# ABS_converter.net
KiCad netlist of a schematic drawn in EAGLE
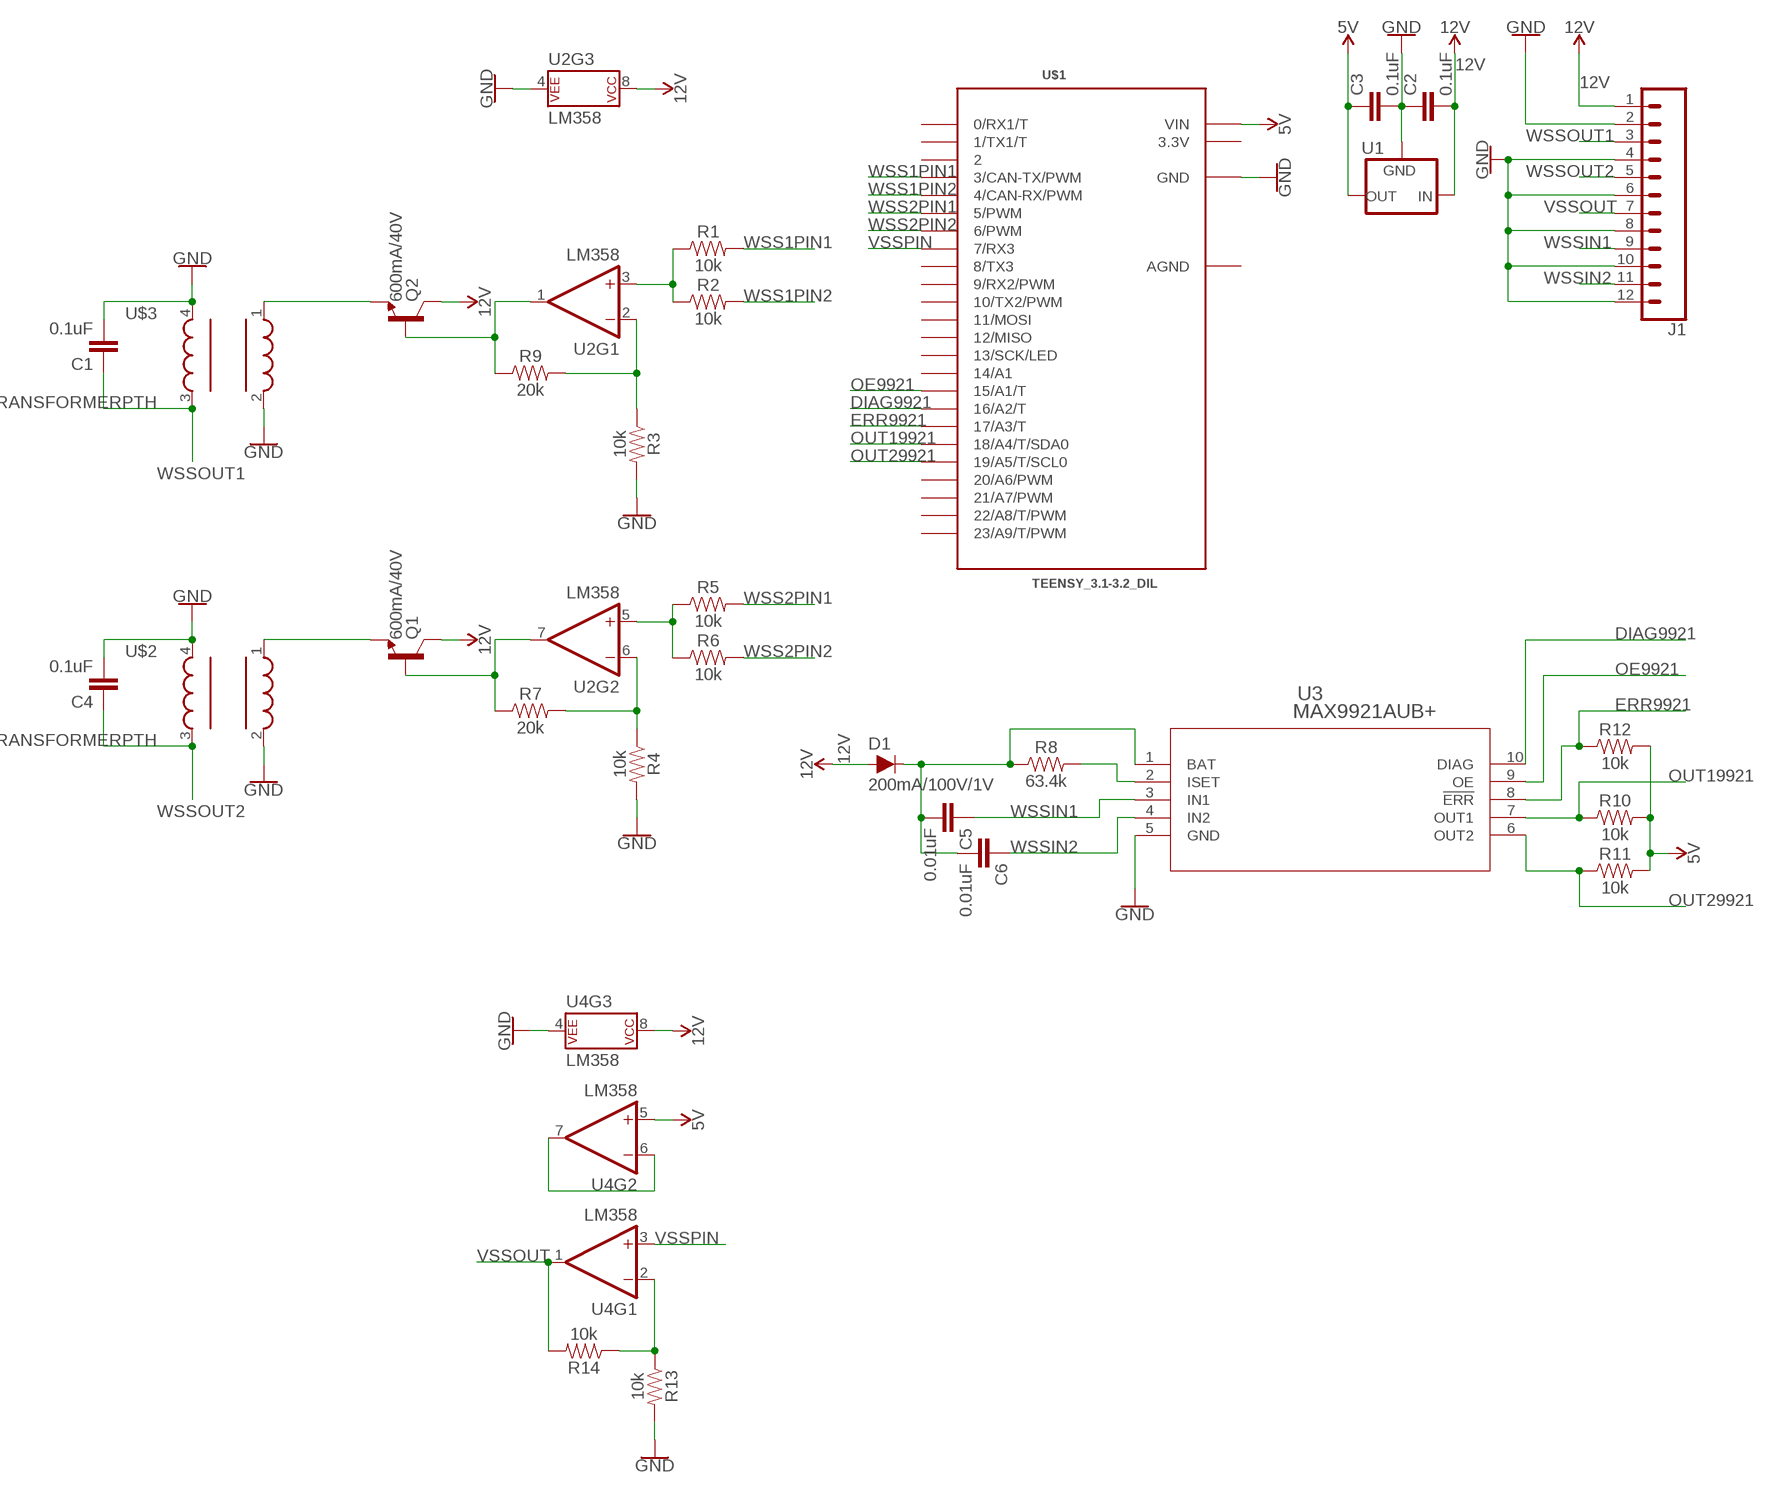
[diagram p0: schematic, sheet 1]

(export (version "E")
  (design (tool "Eeschema 10.0.6"))
  (components
    (comp (ref "C1")
      (value "0.1uF")
      (footprint "eagle-import:CAP-PTH-SMALL-KIT")
      (libsource (lib "eagle-import") (part "0.1UF-KIT-EZ-50V-20%"))
    )
    (comp (ref "C2")
      (value "0.1uF")
      (footprint "eagle-import:CAP-PTH-SMALL-KIT")
      (libsource (lib "eagle-import") (part "0.1UF-KIT-EZ-50V-20%"))
    )
    (comp (ref "C3")
      (value "0.1uF")
      (footprint "eagle-import:CAP-PTH-SMALL-KIT")
      (libsource (lib "eagle-import") (part "0.1UF-KIT-EZ-50V-20%"))
    )
    (comp (ref "C4")
      (value "0.1uF")
      (footprint "eagle-import:CAP-PTH-SMALL-KIT")
      (libsource (lib "eagle-import") (part "0.1UF-KIT-EZ-50V-20%"))
    )
    (comp (ref "C5")
      (value "0.01uF")
      (footprint "eagle-import:CAP-PTH-SMALL-KIT")
      (libsource (lib "eagle-import") (part "0.1UF-KIT-EZ-50V-20%"))
    )
    (comp (ref "C6")
      (value "0.01uF")
      (footprint "eagle-import:CAP-PTH-SMALL-KIT")
      (libsource (lib "eagle-import") (part "0.1UF-KIT-EZ-50V-20%"))
    )
    (comp (ref "D1")
      (value "200mA/100V/1V")
      (footprint "eagle-import:DIODE-1N4148")
      (libsource (lib "eagle-import") (part "DIODE-1N4148"))
    )
    (comp (ref "J1")
      (value "CONN_12")
      (footprint "eagle-import:1X12")
      (libsource (lib "eagle-import") (part "CONN_12"))
    )
    (comp (ref "Q1")
      (value "600mA/40V")
      (footprint "eagle-import:TO-92")
      (libsource (lib "eagle-import") (part "TRANS_NPN-P2N2222A"))
    )
    (comp (ref "Q2")
      (value "600mA/40V")
      (footprint "eagle-import:TO-92")
      (libsource (lib "eagle-import") (part "TRANS_NPN-P2N2222A"))
    )
    (comp (ref "R1")
      (value "10k")
      (footprint "eagle-import:AXIAL-0.3")
      (libsource (lib "eagle-import") (part "10KOHM-HORIZ-1/4W-1%"))
    )
    (comp (ref "R2")
      (value "10k")
      (footprint "eagle-import:AXIAL-0.3")
      (libsource (lib "eagle-import") (part "10KOHM-HORIZ-1/4W-1%"))
    )
    (comp (ref "R3")
      (value "10k")
      (footprint "eagle-import:AXIAL-0.3")
      (libsource (lib "eagle-import") (part "10KOHM-HORIZ-1/4W-1%"))
    )
    (comp (ref "R4")
      (value "10k")
      (footprint "eagle-import:AXIAL-0.3")
      (libsource (lib "eagle-import") (part "10KOHM-HORIZ-1/4W-1%"))
    )
    (comp (ref "R5")
      (value "10k")
      (footprint "eagle-import:AXIAL-0.3")
      (libsource (lib "eagle-import") (part "10KOHM-HORIZ-1/4W-1%"))
    )
    (comp (ref "R6")
      (value "10k")
      (footprint "eagle-import:AXIAL-0.3")
      (libsource (lib "eagle-import") (part "10KOHM-HORIZ-1/4W-1%"))
    )
    (comp (ref "R7")
      (value "20k")
      (footprint "eagle-import:AXIAL-0.3")
      (libsource (lib "eagle-import") (part "RESISTORAXIAL-0.3"))
    )
    (comp (ref "R8")
      (value "63.4k")
      (footprint "eagle-import:AXIAL-0.3")
      (libsource (lib "eagle-import") (part "RESISTORAXIAL-0.3"))
    )
    (comp (ref "R9")
      (value "20k")
      (footprint "eagle-import:AXIAL-0.3")
      (libsource (lib "eagle-import") (part "RESISTORAXIAL-0.3"))
    )
    (comp (ref "R10")
      (value "10k")
      (footprint "eagle-import:AXIAL-0.3")
      (libsource (lib "eagle-import") (part "10KOHM-HORIZ-1/4W-1%"))
    )
    (comp (ref "R11")
      (value "10k")
      (footprint "eagle-import:AXIAL-0.3")
      (libsource (lib "eagle-import") (part "10KOHM-HORIZ-1/4W-1%"))
    )
    (comp (ref "R12")
      (value "10k")
      (footprint "eagle-import:AXIAL-0.3")
      (libsource (lib "eagle-import") (part "10KOHM-HORIZ-1/4W-1%"))
    )
    (comp (ref "R13")
      (value "10k")
      (footprint "eagle-import:AXIAL-0.3")
      (libsource (lib "eagle-import") (part "10KOHM-HORIZ-1/4W-1%"))
    )
    (comp (ref "R14")
      (value "10k")
      (footprint "eagle-import:AXIAL-0.3")
      (libsource (lib "eagle-import") (part "10KOHM-HORIZ-1/4W-1%"))
    )
    (comp (ref "U$1")
      (value "TEENSY_3.1-3.2_DIL")
      (footprint "eagle-import:TEENSY_3.0-3.2&LC_DIL")
      (libsource (lib "eagle-import") (part "TEENSY_3.1-3.2_DIL"))
    )
    (comp (ref "U$2")
      (value "TRANSFORMERPTH")
      (footprint "eagle-import:TRANSFORMER")
      (libsource (lib "eagle-import") (part "TRANSFORMERPTH"))
    )
    (comp (ref "U$3")
      (value "TRANSFORMERPTH")
      (footprint "eagle-import:TRANSFORMER")
      (libsource (lib "eagle-import") (part "TRANSFORMERPTH"))
    )
    (comp (ref "U1")
      (value "V_REG_78XX-TO-220")
      (footprint "eagle-import:TO-220-ALT")
      (libsource (lib "eagle-import") (part "V_REG_78XX-TO-220"))
    )
    (comp (ref "U2")
      (value "LM358")
      (footprint "eagle-import:DIP08")
      (libsource (lib "eagle-import") (part "LM358"))
    )
    (comp (ref "U3")
      (value "MAX9921AUB+")
      (footprint "eagle-import:21-0061L")
      (libsource (lib "eagle-import") (part "MAX9921AUB+"))
    )
    (comp (ref "U4")
      (value "LM358")
      (footprint "eagle-import:DIP08")
      (libsource (lib "eagle-import") (part "LM358"))
    )
  )
  (nets
    (net (code "1") (name "/3.3V") (class "Default")
      (node (ref "U$1") (pin "3.3V") (pinfunction "3.3V_3.3V") (pintype "power_in"))
    )
    (net (code "2") (name "/AGND") (class "Default")
      (node (ref "U$1") (pin "AGND") (pinfunction "AGND_AGND") (pintype "power_in"))
    )
    (net (code "3") (name "/DIAG9921") (class "Default")
      (node (ref "U$1") (pin "16/A2") (pinfunction "16/A2/T_16/A2") (pintype "bidirectional"))
      (node (ref "U3") (pin "10") (pinfunction "DIAG_10") (pintype "input"))
    )
    (net (code "4") (name "/ERR9921") (class "Default")
      (node (ref "R12") (pin "P$1") (pinfunction "1_P$1") (pintype "passive"))
      (node (ref "U$1") (pin "17/A3") (pinfunction "17/A3/T_17/A3") (pintype "bidirectional"))
      (node (ref "U3") (pin "8") (pinfunction "~{ERR}_8") (pintype "output"))
    )
    (net (code "5") (name "/OE9921") (class "Default")
      (node (ref "U$1") (pin "15/A1") (pinfunction "15/A1/T_15/A1") (pintype "bidirectional"))
      (node (ref "U3") (pin "9") (pinfunction "OE_9") (pintype "bidirectional"))
    )
    (net (code "6") (name "/OUT19921") (class "Default")
      (node (ref "R10") (pin "P$1") (pinfunction "1_P$1") (pintype "passive"))
      (node (ref "U$1") (pin "18/A4") (pinfunction "18/A4/T/SDA0_18/A4") (pintype "bidirectional"))
      (node (ref "U3") (pin "7") (pinfunction "OUT1_7") (pintype "output"))
    )
    (net (code "7") (name "/OUT29921") (class "Default")
      (node (ref "R11") (pin "P$1") (pinfunction "1_P$1") (pintype "passive"))
      (node (ref "U$1") (pin "19/A5") (pinfunction "19/A5/T/SCL0_19/A5") (pintype "bidirectional"))
      (node (ref "U3") (pin "6") (pinfunction "OUT2_6") (pintype "output"))
    )
    (net (code "8") (name "/VSSOUT") (class "Default")
      (node (ref "J1") (pin "7") (pinfunction "7_7") (pintype "passive"))
      (node (ref "R14") (pin "P$2") (pinfunction "2_P$2") (pintype "passive"))
      (node (ref "U4") (pin "1") (pinfunction "OUT_1") (pintype "output"))
    )
    (net (code "9") (name "/VSSPIN") (class "Default")
      (node (ref "U$1") (pin "7") (pinfunction "7/RX3_7") (pintype "bidirectional"))
      (node (ref "U4") (pin "3") (pinfunction "+IN_3") (pintype "input"))
    )
    (net (code "10") (name "/WSS1PIN1") (class "Default")
      (node (ref "R1") (pin "P$2") (pinfunction "2_P$2") (pintype "passive"))
      (node (ref "U$1") (pin "3") (pinfunction "3/CAN-TX/PWM_3") (pintype "bidirectional"))
    )
    (net (code "11") (name "/WSS1PIN2") (class "Default")
      (node (ref "R2") (pin "P$2") (pinfunction "2_P$2") (pintype "passive"))
      (node (ref "U$1") (pin "4") (pinfunction "4/CAN-RX/PWM_4") (pintype "bidirectional"))
    )
    (net (code "12") (name "/WSS2PIN1") (class "Default")
      (node (ref "R5") (pin "P$2") (pinfunction "2_P$2") (pintype "passive"))
      (node (ref "U$1") (pin "5") (pinfunction "5/PWM_5") (pintype "bidirectional"))
    )
    (net (code "13") (name "/WSS2PIN2") (class "Default")
      (node (ref "R6") (pin "P$2") (pinfunction "2_P$2") (pintype "passive"))
      (node (ref "U$1") (pin "6") (pinfunction "6/PWM_6") (pintype "bidirectional"))
    )
    (net (code "14") (name "/WSSIN1") (class "Default")
      (node (ref "C5") (pin "1") (pinfunction "1_1") (pintype "passive"))
      (node (ref "J1") (pin "9") (pinfunction "9_9") (pintype "passive"))
      (node (ref "U3") (pin "3") (pinfunction "IN1_3") (pintype "input"))
    )
    (net (code "15") (name "/WSSIN2") (class "Default")
      (node (ref "C6") (pin "1") (pinfunction "1_1") (pintype "passive"))
      (node (ref "J1") (pin "11") (pinfunction "11_11") (pintype "passive"))
      (node (ref "U3") (pin "4") (pinfunction "IN2_4") (pintype "input"))
    )
    (net (code "16") (name "/WSSOUT1") (class "Default")
      (node (ref "C1") (pin "1") (pinfunction "1_1") (pintype "passive"))
      (node (ref "J1") (pin "3") (pinfunction "3_3") (pintype "passive"))
      (node (ref "U$3") (pin "3") (pinfunction "3_3") (pintype "bidirectional"))
    )
    (net (code "17") (name "/WSSOUT2") (class "Default")
      (node (ref "C4") (pin "1") (pinfunction "1_1") (pintype "passive"))
      (node (ref "J1") (pin "5") (pinfunction "5_5") (pintype "passive"))
      (node (ref "U$2") (pin "3") (pinfunction "3_3") (pintype "bidirectional"))
    )
    (net (code "18") (name "5V") (class "Default")
      (node (ref "C3") (pin "1") (pinfunction "1_1") (pintype "passive"))
      (node (ref "R10") (pin "P$2") (pinfunction "2_P$2") (pintype "passive"))
      (node (ref "R11") (pin "P$2") (pinfunction "2_P$2") (pintype "passive"))
      (node (ref "R12") (pin "P$2") (pinfunction "2_P$2") (pintype "passive"))
      (node (ref "U$1") (pin "VIN") (pinfunction "VIN_VIN") (pintype "power_in"))
      (node (ref "U1") (pin "OUT") (pinfunction "OUT_OUT") (pintype "passive"))
      (node (ref "U4") (pin "5") (pinfunction "+IN_5") (pintype "input"))
    )
    (net (code "19") (name "12V") (class "Default")
      (node (ref "C2") (pin "2") (pinfunction "2_2") (pintype "passive"))
      (node (ref "D1") (pin "A") (pinfunction "A_A") (pintype "passive"))
      (node (ref "J1") (pin "1") (pinfunction "1_1") (pintype "passive"))
      (node (ref "Q1") (pin "1") (pinfunction "C_1") (pintype "passive"))
      (node (ref "Q2") (pin "1") (pinfunction "C_1") (pintype "passive"))
      (node (ref "U1") (pin "IN") (pinfunction "IN_IN") (pintype "input"))
      (node (ref "U2") (pin "8") (pinfunction "P$V+_8") (pintype "bidirectional"))
      (node (ref "U4") (pin "8") (pinfunction "P$V+_8") (pintype "bidirectional"))
    )
    (net (code "20") (name "GND") (class "Default")
      (node (ref "C1") (pin "2") (pinfunction "2_2") (pintype "passive"))
      (node (ref "C2") (pin "1") (pinfunction "1_1") (pintype "passive"))
      (node (ref "C3") (pin "2") (pinfunction "2_2") (pintype "passive"))
      (node (ref "C4") (pin "2") (pinfunction "2_2") (pintype "passive"))
      (node (ref "J1") (pin "10") (pinfunction "10_10") (pintype "passive"))
      (node (ref "J1") (pin "12") (pinfunction "12_12") (pintype "passive"))
      (node (ref "J1") (pin "2") (pinfunction "2_2") (pintype "passive"))
      (node (ref "J1") (pin "4") (pinfunction "4_4") (pintype "passive"))
      (node (ref "J1") (pin "6") (pinfunction "6_6") (pintype "passive"))
      (node (ref "J1") (pin "8") (pinfunction "8_8") (pintype "passive"))
      (node (ref "R13") (pin "P$2") (pinfunction "2_P$2") (pintype "passive"))
      (node (ref "R3") (pin "P$2") (pinfunction "2_P$2") (pintype "passive"))
      (node (ref "R4") (pin "P$2") (pinfunction "2_P$2") (pintype "passive"))
      (node (ref "U$1") (pin "GND") (pinfunction "GND_GND") (pintype "power_in"))
      (node (ref "U$2") (pin "2") (pinfunction "2_2") (pintype "bidirectional"))
      (node (ref "U$2") (pin "4") (pinfunction "4_4") (pintype "bidirectional"))
      (node (ref "U$3") (pin "2") (pinfunction "2_2") (pintype "bidirectional"))
      (node (ref "U$3") (pin "4") (pinfunction "4_4") (pintype "bidirectional"))
      (node (ref "U1") (pin "GND") (pinfunction "GND_GND") (pintype "input"))
      (node (ref "U2") (pin "4") (pinfunction "P$V-_4") (pintype "bidirectional"))
      (node (ref "U3") (pin "5") (pinfunction "GND_5") (pintype "power_in"))
      (node (ref "U4") (pin "4") (pinfunction "P$V-_4") (pintype "bidirectional"))
    )
    (net (code "21") (name "Net-(Q1-B)") (class "Default")
      (node (ref "Q1") (pin "2") (pinfunction "B_2") (pintype "passive"))
      (node (ref "R7") (pin "P$1") (pinfunction "1_P$1") (pintype "passive"))
      (node (ref "U2") (pin "7") (pinfunction "OUT_7") (pintype "output"))
    )
    (net (code "22") (name "Net-(Q1-E)") (class "Default")
      (node (ref "Q1") (pin "3") (pinfunction "E_3") (pintype "passive"))
      (node (ref "U$2") (pin "1") (pinfunction "1_1") (pintype "bidirectional"))
    )
    (net (code "23") (name "Net-(Q2-B)") (class "Default")
      (node (ref "Q2") (pin "2") (pinfunction "B_2") (pintype "passive"))
      (node (ref "R9") (pin "P$1") (pinfunction "1_P$1") (pintype "passive"))
      (node (ref "U2") (pin "1") (pinfunction "OUT_1") (pintype "output"))
    )
    (net (code "24") (name "Net-(Q2-E)") (class "Default")
      (node (ref "Q2") (pin "3") (pinfunction "E_3") (pintype "passive"))
      (node (ref "U$3") (pin "1") (pinfunction "1_1") (pintype "bidirectional"))
    )
    (net (code "25") (name "Net-(R1-1)") (class "Default")
      (node (ref "R1") (pin "P$1") (pinfunction "1_P$1") (pintype "passive"))
      (node (ref "R2") (pin "P$1") (pinfunction "1_P$1") (pintype "passive"))
      (node (ref "U2") (pin "3") (pinfunction "+IN_3") (pintype "input"))
    )
    (net (code "26") (name "Net-(R3-1)") (class "Default")
      (node (ref "R3") (pin "P$1") (pinfunction "1_P$1") (pintype "passive"))
      (node (ref "R9") (pin "P$2") (pinfunction "2_P$2") (pintype "passive"))
      (node (ref "U2") (pin "2") (pinfunction "-IN_2") (pintype "input"))
    )
    (net (code "27") (name "Net-(R4-1)") (class "Default")
      (node (ref "R4") (pin "P$1") (pinfunction "1_P$1") (pintype "passive"))
      (node (ref "R7") (pin "P$2") (pinfunction "2_P$2") (pintype "passive"))
      (node (ref "U2") (pin "6") (pinfunction "-IN_6") (pintype "input"))
    )
    (net (code "28") (name "Net-(R5-1)") (class "Default")
      (node (ref "R5") (pin "P$1") (pinfunction "1_P$1") (pintype "passive"))
      (node (ref "R6") (pin "P$1") (pinfunction "1_P$1") (pintype "passive"))
      (node (ref "U2") (pin "5") (pinfunction "+IN_5") (pintype "input"))
    )
    (net (code "29") (name "Net-(R8-1)") (class "Default")
      (node (ref "C5") (pin "2") (pinfunction "2_2") (pintype "passive"))
      (node (ref "C6") (pin "2") (pinfunction "2_2") (pintype "passive"))
      (node (ref "D1") (pin "C") (pinfunction "C_C") (pintype "passive"))
      (node (ref "R8") (pin "P$1") (pinfunction "1_P$1") (pintype "passive"))
      (node (ref "U3") (pin "1") (pinfunction "BAT_1") (pintype "power_in"))
    )
    (net (code "30") (name "Net-(R8-2)") (class "Default")
      (node (ref "R8") (pin "P$2") (pinfunction "2_P$2") (pintype "passive"))
      (node (ref "U3") (pin "2") (pinfunction "ISET_2") (pintype "input"))
    )
    (net (code "31") (name "Net-(R13-1)") (class "Default")
      (node (ref "R13") (pin "P$1") (pinfunction "1_P$1") (pintype "passive"))
      (node (ref "R14") (pin "P$1") (pinfunction "1_P$1") (pintype "passive"))
      (node (ref "U4") (pin "2") (pinfunction "-IN_2") (pintype "input"))
    )
    (net (code "32") (name "Net-(U4B--IN)") (class "Default")
      (node (ref "U4") (pin "6") (pinfunction "-IN_6") (pintype "input"))
      (node (ref "U4") (pin "7") (pinfunction "OUT_7") (pintype "output"))
    )
    (net (code "33") (name "unconnected-(U$1-0{slash}RX1{slash}T-Pad0)") (class "Default")
      (node (ref "U$1") (pin "0") (pinfunction "0/RX1/T_0") (pintype "bidirectional"))
    )
    (net (code "34") (name "unconnected-(U$1-1{slash}TX1{slash}T-Pad1)") (class "Default")
      (node (ref "U$1") (pin "1") (pinfunction "1/TX1/T_1") (pintype "bidirectional"))
    )
    (net (code "35") (name "unconnected-(U$1-8{slash}TX3-Pad8)") (class "Default")
      (node (ref "U$1") (pin "8") (pinfunction "8/TX3_8") (pintype "bidirectional"))
    )
    (net (code "36") (name "unconnected-(U$1-9{slash}RX2{slash}PWM-Pad9)") (class "Default")
      (node (ref "U$1") (pin "9") (pinfunction "9/RX2/PWM_9") (pintype "bidirectional"))
    )
    (net (code "37") (name "unconnected-(U$1-10{slash}TX2{slash}PWM-Pad10)") (class "Default")
      (node (ref "U$1") (pin "10") (pinfunction "10/TX2/PWM_10") (pintype "bidirectional"))
    )
    (net (code "38") (name "unconnected-(U$1-11{slash}MOSI-Pad11)") (class "Default")
      (node (ref "U$1") (pin "11") (pinfunction "11/MOSI_11") (pintype "bidirectional"))
    )
    (net (code "39") (name "unconnected-(U$1-12{slash}MISO-Pad12)") (class "Default")
      (node (ref "U$1") (pin "12") (pinfunction "12/MISO_12") (pintype "bidirectional"))
    )
    (net (code "40") (name "unconnected-(U$1-13{slash}SCK{slash}LED-Pad13)") (class "Default")
      (node (ref "U$1") (pin "13") (pinfunction "13/SCK/LED_13") (pintype "bidirectional"))
    )
    (net (code "41") (name "unconnected-(U$1-14{slash}A1-Pad14{slash}A0)") (class "Default")
      (node (ref "U$1") (pin "14/A0") (pinfunction "14/A1_14/A0") (pintype "bidirectional"))
    )
    (net (code "42") (name "unconnected-(U$1-20{slash}A6{slash}PWM-Pad20{slash}A6)") (class "Default")
      (node (ref "U$1") (pin "20/A6") (pinfunction "20/A6/PWM_20/A6") (pintype "bidirectional"))
    )
    (net (code "43") (name "unconnected-(U$1-21{slash}A7{slash}PWM-Pad21{slash}A7)") (class "Default")
      (node (ref "U$1") (pin "21/A7") (pinfunction "21/A7/PWM_21/A7") (pintype "bidirectional"))
    )
    (net (code "44") (name "unconnected-(U$1-22{slash}A8{slash}T{slash}PWM-Pad22{slash}A8)") (class "Default")
      (node (ref "U$1") (pin "22/A8") (pinfunction "22/A8/T/PWM_22/A8") (pintype "bidirectional"))
    )
    (net (code "45") (name "unconnected-(U$1-23{slash}A9{slash}T{slash}PWM-Pad23{slash}A9)") (class "Default")
      (node (ref "U$1") (pin "23/A9") (pinfunction "23/A9/T/PWM_23/A9") (pintype "bidirectional"))
    )
    (net (code "46") (name "unconnected-(U$1-Pad2)") (class "Default")
      (node (ref "U$1") (pin "2") (pinfunction "2_2") (pintype "bidirectional"))
    )
  )
)
